# Control.net
KiCad netlist of a schematic drawn in Altium Designer
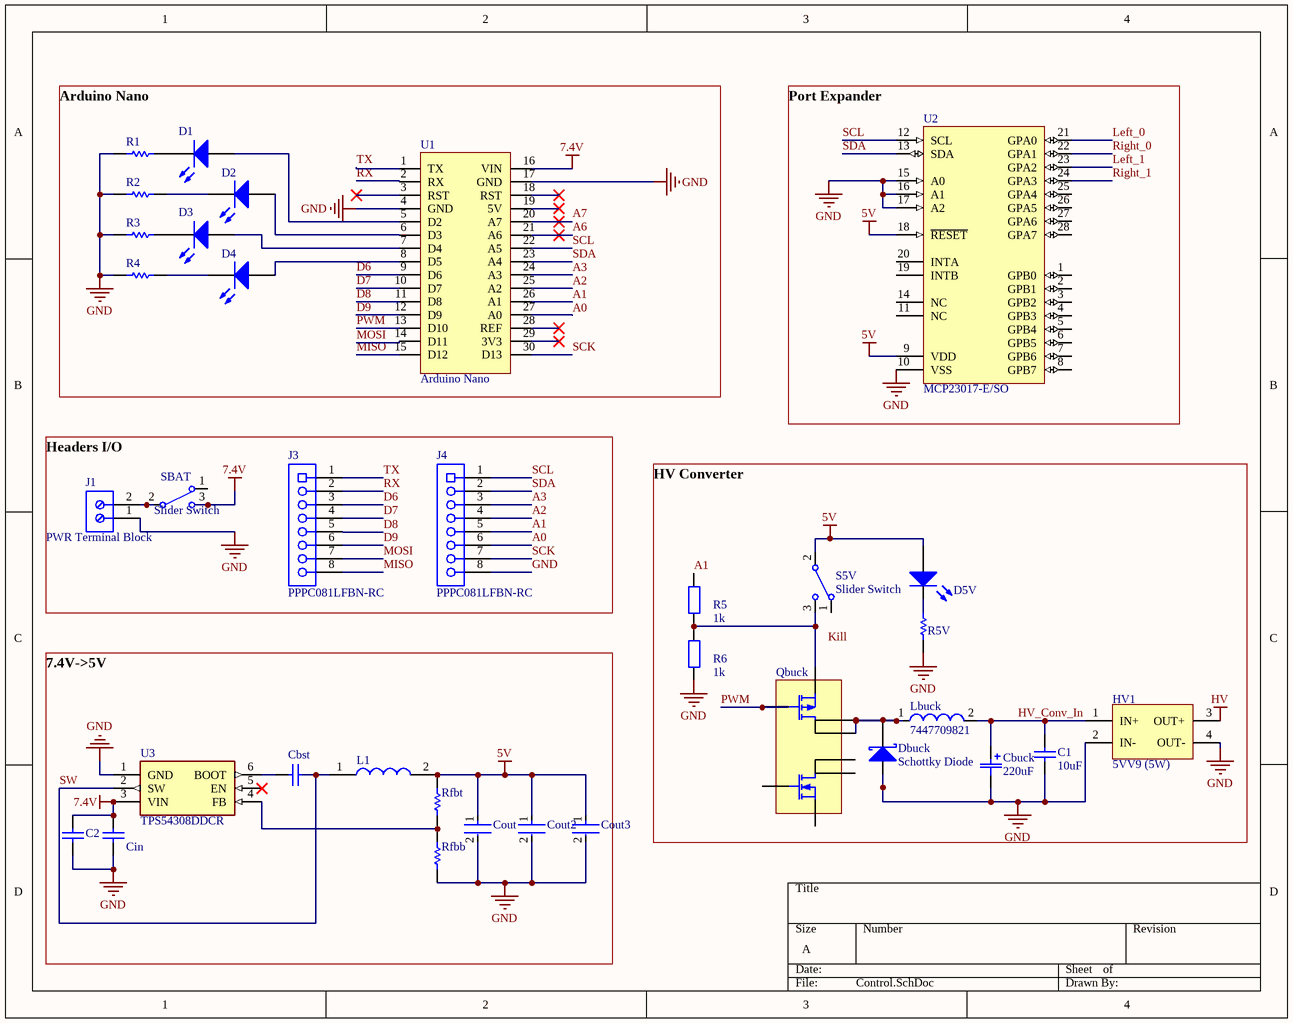
[diagram p0: Control.SchDoc]

(export (version "E")
  (design (tool "Eeschema 10.0.6"))
  (components
    (comp (ref "C1")
      (value "10uF")
      (footprint "1206 CAP")
      (description "1276-3038-6-ND\r\nManufacturer: CL31A106KAHNFNE")
      (fields (field (name "Comment") "Capacitor 10uF"))
      (libsource (lib "Schlib") (part "Capacitor 10uF"))
    )
    (comp (ref "C2")
      (value "C0805C104K5RACTU")
      (footprint "CAPC2013X88X50NL20T25")
      (fields (field (name "MANUFACTURER") "Kemet"))
      (libsource (lib "Altium Content Vault") (part "CAP"))
    )
    (comp (ref "Cbst")
      (value "CAP 100nF 50V 0805(2012)")
      (footprint "CAPC0805(2012)100_M")
      (description "CAP 100nF 50V ±20% 0805 (2012 Metric) Thickness 1mm SMD")
      (fields (field (name "TOLERANCE") "Â±20%"))
      (libsource (lib "Altium Content Vault") (part "CAP"))
    )
    (comp (ref "Cbuck")
      (value "220uF")
      (footprint "SMD 7343 - Pol")
      (description "Digikey: ‎399-8415-1-ND‎\r\nManufacturer: ‎T491X227K016AT‎")
      (fields
        (field (name "Comment") "Capacitor 220uF (Polarized)")
        (field (name "PUBLISHER") "Altium Limited")
      )
      (libsource (lib "Schlib") (part "Capacitor 220uF (Polarized)"))
    )
    (comp (ref "Cin")
      (value "GRM32ER61C226KE20L")
      (footprint "MURA-1210_H_2.7_L")
      (fields (field (name "MANUFACTURER") "Murata") (field (name "TOLERANCE") "±10%"))
      (libsource (lib "Altium Content Vault") (part "CAP-NP-2"))
    )
    (comp (ref "Cout")
      (value "CL32B106KBJNNWE")
      (footprint "FP-CL32-IPC_B")
      (description "Cap Ceramic 10uF 50V X7R ±10% SMD 1210 +125°C Embossed T/R")
      (fields (field (name "TOLERANCE") "10%"))
      (libsource (lib "Altium Content Vault") (part "b4654b650e69147ec39a6b967a45e02"))
    )
    (comp (ref "Cout2")
      (value "CL32B106KBJNNWE")
      (footprint "FP-CL32-IPC_B")
      (description "Cap Ceramic 10uF 50V X7R ±10% SMD 1210 +125°C Embossed T/R")
      (fields (field (name "TOLERANCE") "10%"))
      (libsource (lib "Altium Content Vault") (part "b4654b650e69147ec39a6b967a45e02"))
    )
    (comp (ref "Cout3")
      (value "CL32B106KBJNNWE")
      (footprint "FP-CL32-IPC_B")
      (description "Cap Ceramic 10uF 50V X7R ±10% SMD 1210 +125°C Embossed T/R")
      (fields (field (name "TOLERANCE") "10%"))
      (libsource (lib "Altium Content Vault") (part "b4654b650e69147ec39a6b967a45e02"))
    )
    (comp (ref "D1")
      (value "150080SS75000")
      (footprint "0805_A")
      (description "SMD mono-color Chip LED, WL-SMCW, Super Red")
      (fields (field (name "MANUFACTURER") "Wuerth Elektronik"))
      (libsource (lib "Altium Content Vault") (part "WE-LED_K1A2-2"))
    )
    (comp (ref "D2")
      (value "150080VS75000")
      (footprint "0805_A")
      (description "SMD mono-color Chip LED, WL-SMCW, Bright Green")
      (fields (field (name "MANUFACTURER") "Wuerth Elektronik"))
      (libsource (lib "Altium Content Vault") (part "WE-LED_K1A2-2"))
    )
    (comp (ref "D3")
      (value "150080SS75000")
      (footprint "0805_A")
      (description "SMD mono-color Chip LED, WL-SMCW, Super Red")
      (fields (field (name "MANUFACTURER") "Wuerth Elektronik"))
      (libsource (lib "Altium Content Vault") (part "WE-LED_K1A2-2"))
    )
    (comp (ref "D4")
      (value "150080VS75000")
      (footprint "0805_A")
      (description "SMD mono-color Chip LED, WL-SMCW, Bright Green")
      (fields (field (name "MANUFACTURER") "Wuerth Elektronik"))
      (libsource (lib "Altium Content Vault") (part "WE-LED_K1A2-2"))
    )
    (comp (ref "D5V")
      (value "150080VS75000")
      (footprint "0805_A")
      (description "SMD mono-color Chip LED, WL-SMCW, Bright Green")
      (fields (field (name "MANUFACTURER") "Wuerth Elektronik"))
      (libsource (lib "Altium Content Vault") (part "WE-LED_K1A2-2"))
    )
    (comp (ref "Dbuck")
      (value "Schottky Diode")
      (footprint "Schottky Diode")
      (libsource (lib "Schlib") (part "Schottky Diode"))
    )
    (comp (ref "HV1") (value "5VV9 (5W)") (footprint "5VV9") (libsource (lib "Schlib1") (part "5VV9")))
    (comp (ref "J1")
      (value "PWR Terminal Block")
      (footprint "691103110002")
      (description "Series 1031 - 3.50 mm Horizontal Entry Modular with Pressure Clamp WR-TBL, 2 pin")
      (fields
        (field (name "MANUFACTURER") "Wurth Elektronik")
        (field (name "PART NUMBER") "691103110002")
        (field (name "PUBLISHER") "WurthElektronik")
      )
      (libsource (lib "Altium Content Vault") (part "WE-CN-1P-F-TB2"))
    )
    (comp (ref "J3")
      (value "PPPC081LFBN-RC")
      (footprint "SLIN-PPPC081LFBN-RC_V")
      (libsource (lib "Altium Content Vault") (part "CN-1P-F-R8"))
    )
    (comp (ref "J4")
      (value "PPPC081LFBN-RC")
      (footprint "SLIN-PPPC081LFBN-RC_V")
      (libsource (lib "Altium Content Vault") (part "CN-1P-F-R8"))
    )
    (comp (ref "L1")
      (value "7443251600")
      (footprint "SamacSys:WE-HCI_105023")
      (description "Inductor")
      (fields (field (name "MOUSER PART NUMBER") "710-7443251600"))
      (libsource (lib "*") (part "7443251600"))
    )
    (comp (ref "Lbuck")
      (value "7447709821")
      (footprint "WE-PD-XXL")
      (description "SMD-Shielded Power Inductor WE-PD, L = 820 µH")
      (libsource (lib "Altium Content Vault") (part "PAS-IND-INDUCTOR-2"))
    )
    (comp (ref "Qbuck")
      (value "Dual MOSFET")
      (footprint "SO-8")
      (libsource (lib "Schlib") (part "Dual MOSFET"))
    )
    (comp (ref "R1")
      (value "ERJ-6GEYJ161V")
      (footprint "RESC0805(2012)_N")
      (description "160R 0.125W 5% 0805 (2012 Metric)  SMD")
      (fields (field (name "TOLERANCE") "5 %") (field (name "POWER") "0.125 W"))
      (libsource (lib "Altium Content Vault") (part "RES"))
    )
    (comp (ref "R2")
      (value "ERJ-6GEYJ161V")
      (footprint "RESC0805(2012)_N")
      (description "160R 0.125W 5% 0805 (2012 Metric)  SMD")
      (fields (field (name "TOLERANCE") "5 %") (field (name "POWER") "0.125 W"))
      (libsource (lib "Altium Content Vault") (part "RES"))
    )
    (comp (ref "R3")
      (value "ERJ-6GEYJ161V")
      (footprint "RESC0805(2012)_N")
      (description "160R 0.125W 5% 0805 (2012 Metric)  SMD")
      (fields (field (name "TOLERANCE") "5 %") (field (name "POWER") "0.125 W"))
      (libsource (lib "Altium Content Vault") (part "RES"))
    )
    (comp (ref "R4")
      (value "ERJ-6GEYJ161V")
      (footprint "RESC0805(2012)_N")
      (description "160R 0.125W 5% 0805 (2012 Metric)  SMD")
      (fields (field (name "TOLERANCE") "5 %") (field (name "POWER") "0.125 W"))
      (libsource (lib "Altium Content Vault") (part "RES"))
    )
    (comp (ref "R5")
      (value "1k")
      (footprint "1206 R")
      (description "‎541-2245-1-ND‎\r\nManufacturer: ‎RCA12061K00FKEA‎")
      (fields (field (name "Comment") "Resistor"))
      (libsource (lib "Schlib") (part "Resistor 1k"))
    )
    (comp (ref "R5V")
      (value "ERJ-6GEYJ161V")
      (footprint "RESC0805(2012)_N")
      (description "160R 0.125W 5% 0805 (2012 Metric)  SMD")
      (fields (field (name "TOLERANCE") "5 %") (field (name "POWER") "0.125 W"))
      (libsource (lib "Altium Content Vault") (part "RES"))
    )
    (comp (ref "R6")
      (value "1k")
      (footprint "1206 R")
      (description "‎541-2245-1-ND‎\r\nManufacturer: ‎RCA12061K00FKEA‎")
      (fields (field (name "Comment") "Resistor"))
      (libsource (lib "Schlib") (part "Resistor 1k"))
    )
    (comp (ref "Rfbb")
      (value "CRCW080513K7FKEA")
      (footprint "RESC2013X50X30ML20T20")
      (fields (field (name "MANUFACTURER") "Vishay Dale"))
      (libsource (lib "Altium Content Vault") (part "RES"))
    )
    (comp (ref "Rfbt")
      (value "CRCW0805100KFKEA")
      (footprint "RESC2013X50X30NL20T20")
      (fields (field (name "MANUFACTURER") "Vishay Dale"))
      (libsource (lib "Altium Content Vault") (part "RES"))
    )
    (comp (ref "S5V")
      (value "Slider Switch")
      (footprint "Slide Switch")
      (description "Digikey: ‎563-1571-ND‎\r\nManufacturer:‎ MHS122-1‎")
      (fields (field (name "PUBLISHER") "Altium Limited"))
      (libsource (lib "Schlib") (part "Switch-SPST"))
    )
    (comp (ref "SBAT")
      (value "Slider Switch")
      (footprint "Slide Switch")
      (description "Digikey: ‎563-1571-ND‎\r\nManufacturer:‎ MHS122-1‎")
      (fields (field (name "PUBLISHER") "Altium Limited"))
      (libsource (lib "Schlib") (part "Switch-SPST"))
    )
    (comp (ref "U1")
      (value "Arduino Nano")
      (footprint "Arduino Nano")
      (libsource (lib "Schlib") (part "Arduino Nano"))
    )
    (comp (ref "U2")
      (value "MCP23017-E/SO")
      (footprint "SOIC-SO28_N")
      (description "16-Bit I/O Expander with Serial Interface, 28-Pin SOIC, Extended Temperature")
      (libsource (lib "Altium Content Vault") (part "PR-BUSIC-MCP23017-28"))
    )
    (comp (ref "U3")
      (value "TPS54308DDCR")
      (footprint "SamacSys:SOT95P280X100-6N")
      (description "Power Supply")
      (fields (field (name "MOUSER PART NUMBER") "595-TPS54308DDCR"))
      (libsource (lib "*") (part "TPS54308DDCR"))
    )
  )
  (nets
    (net (code "2") (name "/A0") (class "Default")
      (node (ref "J4") (pin "6") (pinfunction "6_6") (pintype "passive"))
      (node (ref "U1") (pin "27") (pinfunction "A0_27") (pintype "passive"))
    )
    (net (code "3") (name "/A1") (class "Default")
      (node (ref "J4") (pin "5") (pinfunction "5_5") (pintype "passive"))
      (node (ref "R5") (pin "2") (pinfunction "2_2") (pintype "passive"))
      (node (ref "U1") (pin "26") (pinfunction "A1_26") (pintype "passive"))
    )
    (net (code "4") (name "/A2") (class "Default")
      (node (ref "J4") (pin "4") (pinfunction "4_4") (pintype "passive"))
      (node (ref "U1") (pin "25") (pinfunction "A2_25") (pintype "passive"))
    )
    (net (code "5") (name "/A3") (class "Default")
      (node (ref "J4") (pin "3") (pinfunction "3_3") (pintype "passive"))
      (node (ref "U1") (pin "24") (pinfunction "A3_24") (pintype "passive"))
    )
    (net (code "6") (name "/A6") (class "Default")
      (node (ref "U1") (pin "21") (pinfunction "A6_21") (pintype "passive"))
    )
    (net (code "8") (name "/A7") (class "Default")
      (node (ref "U1") (pin "20") (pinfunction "A7_20") (pintype "passive"))
    )
    (net (code "9") (name "/D6") (class "Default")
      (node (ref "J3") (pin "3") (pinfunction "3_3") (pintype "passive"))
      (node (ref "U1") (pin "9") (pinfunction "D6_9") (pintype "passive"))
    )
    (net (code "10") (name "/D7") (class "Default")
      (node (ref "J3") (pin "4") (pinfunction "4_4") (pintype "passive"))
      (node (ref "U1") (pin "10") (pinfunction "D7_10") (pintype "passive"))
    )
    (net (code "11") (name "/D8") (class "Default")
      (node (ref "J3") (pin "5") (pinfunction "5_5") (pintype "passive"))
      (node (ref "U1") (pin "11") (pinfunction "D8_11") (pintype "passive"))
    )
    (net (code "12") (name "/D9") (class "Default")
      (node (ref "J3") (pin "6") (pinfunction "6_6") (pintype "passive"))
      (node (ref "U1") (pin "12") (pinfunction "D9_12") (pintype "passive"))
    )
    (net (code "14") (name "/HV_Conv_In") (class "Default")
      (node (ref "C1") (pin "2") (pinfunction "2_2") (pintype "passive"))
      (node (ref "Cbuck") (pin "1") (pinfunction "1_1") (pintype "passive"))
      (node (ref "HV1") (pin "1") (pinfunction "IN+_1") (pintype "passive"))
      (node (ref "Lbuck") (pin "2") (pinfunction "2_2") (pintype "passive"))
    )
    (net (code "15") (name "/Left_0") (class "Default")
      (node (ref "U2") (pin "21") (pinfunction "GPA0_21") (pintype "bidirectional"))
    )
    (net (code "16") (name "/Left_1") (class "Default")
      (node (ref "U2") (pin "23") (pinfunction "GPA2_23") (pintype "bidirectional"))
    )
    (net (code "17") (name "/MISO") (class "Default")
      (node (ref "J3") (pin "8") (pinfunction "8_8") (pintype "passive"))
      (node (ref "U1") (pin "15") (pinfunction "D12_15") (pintype "passive"))
    )
    (net (code "18") (name "/MOSI") (class "Default")
      (node (ref "J3") (pin "7") (pinfunction "7_7") (pintype "passive"))
      (node (ref "U1") (pin "14") (pinfunction "D11_14") (pintype "passive"))
    )
    (net (code "19") (name "/PWM") (class "Default")
      (node (ref "Qbuck") (pin "4") (pinfunction "4_4") (pintype "passive"))
      (node (ref "U1") (pin "13") (pinfunction "D10_13") (pintype "passive"))
    )
    (net (code "20") (name "/RX") (class "Default")
      (node (ref "J3") (pin "2") (pinfunction "2_2") (pintype "passive"))
      (node (ref "U1") (pin "2") (pinfunction "RX_2") (pintype "passive"))
    )
    (net (code "21") (name "/Right_0") (class "Default")
      (node (ref "U2") (pin "22") (pinfunction "GPA1_22") (pintype "bidirectional"))
    )
    (net (code "22") (name "/Right_1") (class "Default")
      (node (ref "U2") (pin "24") (pinfunction "GPA3_24") (pintype "bidirectional"))
    )
    (net (code "23") (name "/SCK") (class "Default")
      (node (ref "J4") (pin "7") (pinfunction "7_7") (pintype "passive"))
      (node (ref "U1") (pin "30") (pinfunction "D13_30") (pintype "passive"))
    )
    (net (code "24") (name "/SCL") (class "Default")
      (node (ref "J4") (pin "1") (pinfunction "1_1") (pintype "passive"))
      (node (ref "U1") (pin "22") (pinfunction "A5_22") (pintype "passive"))
      (node (ref "U2") (pin "12") (pinfunction "SCL_12") (pintype "input"))
    )
    (net (code "25") (name "/SDA") (class "Default")
      (node (ref "J4") (pin "2") (pinfunction "2_2") (pintype "passive"))
      (node (ref "U1") (pin "23") (pinfunction "A4_23") (pintype "passive"))
      (node (ref "U2") (pin "13") (pinfunction "SDA_13") (pintype "bidirectional"))
    )
    (net (code "26") (name "/SW") (class "Default")
      (node (ref "Cbst") (pin "2") (pinfunction "2_2") (pintype "passive"))
      (node (ref "L1") (pin "1") (pinfunction "1_1") (pintype "passive"))
      (node (ref "U3") (pin "2") (pinfunction "SW_2") (pintype "output"))
    )
    (net (code "27") (name "/TX") (class "Default")
      (node (ref "J3") (pin "1") (pinfunction "1_1") (pintype "passive"))
      (node (ref "U1") (pin "1") (pinfunction "TX_1") (pintype "passive"))
    )
    (net (code "28") (name "5V") (class "Default")
      (node (ref "Cout") (pin "1") (pinfunction "1_1") (pintype "passive"))
      (node (ref "Cout2") (pin "1") (pinfunction "1_1") (pintype "passive"))
      (node (ref "Cout3") (pin "1") (pinfunction "1_1") (pintype "passive"))
      (node (ref "D5V") (pin "2") (pinfunction "A_2") (pintype "passive"))
      (node (ref "L1") (pin "2") (pinfunction "2_2") (pintype "passive"))
      (node (ref "Rfbt") (pin "2") (pinfunction "2_2") (pintype "passive"))
      (node (ref "S5V") (pin "2") (pinfunction "NO_2") (pintype "passive"))
      (node (ref "U2") (pin "18") (pinfunction "~{RESET}_18") (pintype "input"))
      (node (ref "U2") (pin "9") (pinfunction "VDD_9") (pintype "power_in"))
    )
    (net (code "29") (name "7.4V") (class "Default")
      (node (ref "C2") (pin "2") (pinfunction "2_2") (pintype "passive"))
      (node (ref "Cin") (pin "2") (pinfunction "2_2") (pintype "passive"))
      (node (ref "SBAT") (pin "3") (pinfunction "3_3") (pintype "passive"))
      (node (ref "U1") (pin "16") (pinfunction "VIN_16") (pintype "passive"))
      (node (ref "U3") (pin "3") (pinfunction "VIN_3") (pintype "power_in"))
    )
    (net (code "30") (name "GND") (class "Default")
      (node (ref "C1") (pin "1") (pinfunction "1_1") (pintype "passive"))
      (node (ref "C2") (pin "1") (pinfunction "1_1") (pintype "passive"))
      (node (ref "Cbuck") (pin "2") (pinfunction "2_2") (pintype "passive"))
      (node (ref "Cin") (pin "1") (pinfunction "1_1") (pintype "passive"))
      (node (ref "Cout") (pin "2") (pinfunction "2_2") (pintype "passive"))
      (node (ref "Cout2") (pin "2") (pinfunction "2_2") (pintype "passive"))
      (node (ref "Cout3") (pin "2") (pinfunction "2_2") (pintype "passive"))
      (node (ref "Dbuck") (pin "1") (pinfunction "A_1") (pintype "passive"))
      (node (ref "HV1") (pin "2") (pinfunction "IN-_2") (pintype "passive"))
      (node (ref "HV1") (pin "4") (pinfunction "OUT-_4") (pintype "passive"))
      (node (ref "J1") (pin "1") (pinfunction "1_1") (pintype "passive"))
      (node (ref "J4") (pin "8") (pinfunction "8_8") (pintype "passive"))
      (node (ref "R1") (pin "1") (pinfunction "1_1") (pintype "passive"))
      (node (ref "R2") (pin "1") (pinfunction "1_1") (pintype "passive"))
      (node (ref "R3") (pin "1") (pinfunction "1_1") (pintype "passive"))
      (node (ref "R4") (pin "1") (pinfunction "1_1") (pintype "passive"))
      (node (ref "R5V") (pin "1") (pinfunction "1_1") (pintype "passive"))
      (node (ref "R6") (pin "1") (pinfunction "1_1") (pintype "passive"))
      (node (ref "Rfbb") (pin "1") (pinfunction "1_1") (pintype "passive"))
      (node (ref "U1") (pin "17") (pinfunction "GND_17") (pintype "passive"))
      (node (ref "U1") (pin "4") (pinfunction "GND_4") (pintype "passive"))
      (node (ref "U2") (pin "10") (pinfunction "VSS_10") (pintype "power_in"))
      (node (ref "U2") (pin "15") (pinfunction "A0_15") (pintype "input"))
      (node (ref "U2") (pin "16") (pinfunction "A1_16") (pintype "input"))
      (node (ref "U2") (pin "17") (pinfunction "A2_17") (pintype "input"))
      (node (ref "U3") (pin "1") (pinfunction "GND_1") (pintype "power_in"))
    )
    (net (code "31") (name "HV") (class "Default")
      (node (ref "HV1") (pin "3") (pinfunction "OUT+_3") (pintype "passive"))
    )
    (net (code "32") (name "Net-(D1-A)") (class "Default")
      (node (ref "D1") (pin "2") (pinfunction "A_2") (pintype "passive"))
      (node (ref "U1") (pin "5") (pinfunction "D2_5") (pintype "passive"))
    )
    (net (code "33") (name "Net-(D1-K)") (class "Default")
      (node (ref "D1") (pin "1") (pinfunction "K_1") (pintype "passive"))
      (node (ref "R1") (pin "2") (pinfunction "2_2") (pintype "passive"))
    )
    (net (code "34") (name "Net-(D2-A)") (class "Default")
      (node (ref "D2") (pin "2") (pinfunction "A_2") (pintype "passive"))
      (node (ref "U1") (pin "6") (pinfunction "D3_6") (pintype "passive"))
    )
    (net (code "35") (name "Net-(D2-K)") (class "Default")
      (node (ref "D2") (pin "1") (pinfunction "K_1") (pintype "passive"))
      (node (ref "R2") (pin "2") (pinfunction "2_2") (pintype "passive"))
    )
    (net (code "36") (name "Net-(D3-A)") (class "Default")
      (node (ref "D3") (pin "2") (pinfunction "A_2") (pintype "passive"))
      (node (ref "U1") (pin "7") (pinfunction "D4_7") (pintype "passive"))
    )
    (net (code "37") (name "Net-(D3-K)") (class "Default")
      (node (ref "D3") (pin "1") (pinfunction "K_1") (pintype "passive"))
      (node (ref "R3") (pin "2") (pinfunction "2_2") (pintype "passive"))
    )
    (net (code "38") (name "Net-(D4-A)") (class "Default")
      (node (ref "D4") (pin "2") (pinfunction "A_2") (pintype "passive"))
      (node (ref "U1") (pin "8") (pinfunction "D5_8") (pintype "passive"))
    )
    (net (code "39") (name "Net-(D4-K)") (class "Default")
      (node (ref "D4") (pin "1") (pinfunction "K_1") (pintype "passive"))
      (node (ref "R4") (pin "2") (pinfunction "2_2") (pintype "passive"))
    )
    (net (code "40") (name "Net-(D5V-K)") (class "Default")
      (node (ref "D5V") (pin "1") (pinfunction "K_1") (pintype "passive"))
      (node (ref "R5V") (pin "2") (pinfunction "2_2") (pintype "passive"))
    )
    (net (code "41") (name "Net-(Dbuck-K)") (class "Default")
      (node (ref "Dbuck") (pin "2") (pinfunction "K_2") (pintype "passive"))
      (node (ref "Lbuck") (pin "1") (pinfunction "1_1") (pintype "passive"))
      (node (ref "Qbuck") (pin "5") (pinfunction "5_5") (pintype "passive"))
      (node (ref "Qbuck") (pin "6") (pinfunction "6_6") (pintype "passive"))
    )
    (net (code "42") (name "Net-(Qbuck-Pad3)") (class "Default")
      (node (ref "Qbuck") (pin "3") (pinfunction "3_3") (pintype "passive"))
      (node (ref "R5") (pin "1") (pinfunction "1_1") (pintype "passive"))
      (node (ref "R6") (pin "2") (pinfunction "2_2") (pintype "passive"))
      (node (ref "S5V") (pin "3") (pinfunction "3_3") (pintype "passive"))
    )
    (net (code "43") (name "Net-(SBAT-NO)") (class "Default")
      (node (ref "J1") (pin "2") (pinfunction "2_2") (pintype "passive"))
      (node (ref "SBAT") (pin "2") (pinfunction "NO_2") (pintype "passive"))
    )
    (net (code "44") (name "Net-(U3-BOOT)") (class "Default")
      (node (ref "Cbst") (pin "1") (pinfunction "1_1") (pintype "passive"))
      (node (ref "U3") (pin "6") (pinfunction "BOOT_6") (pintype "output"))
    )
    (net (code "45") (name "Net-(U3-FB)") (class "Default")
      (node (ref "Rfbb") (pin "2") (pinfunction "2_2") (pintype "passive"))
      (node (ref "Rfbt") (pin "1") (pinfunction "1_1") (pintype "passive"))
      (node (ref "U3") (pin "4") (pinfunction "FB_4") (pintype "input"))
    )
    (net (code "46") (name "unconnected-(Qbuck-Pad1)") (class "Default")
      (node (ref "Qbuck") (pin "1") (pinfunction "1_1") (pintype "passive"))
    )
    (net (code "47") (name "unconnected-(Qbuck-Pad2)") (class "Default")
      (node (ref "Qbuck") (pin "2") (pinfunction "2_2") (pintype "passive"))
    )
    (net (code "48") (name "unconnected-(Qbuck-Pad7)") (class "Default")
      (node (ref "Qbuck") (pin "7") (pinfunction "7_7") (pintype "passive"))
    )
    (net (code "49") (name "unconnected-(Qbuck-Pad8)") (class "Default")
      (node (ref "Qbuck") (pin "8") (pinfunction "8_8") (pintype "passive"))
    )
    (net (code "50") (name "unconnected-(S5V-COMMON-Pad1)") (class "Default")
      (node (ref "S5V") (pin "1") (pinfunction "COMMON_1") (pintype "passive"))
    )
    (net (code "51") (name "unconnected-(SBAT-COMMON-Pad1)") (class "Default")
      (node (ref "SBAT") (pin "1") (pinfunction "COMMON_1") (pintype "passive"))
    )
    (net (code "52") (name "unconnected-(U1-3V3-Pad29)") (class "Default")
      (node (ref "U1") (pin "29") (pinfunction "3V3_29") (pintype "passive+no_connect"))
    )
    (net (code "53") (name "unconnected-(U1-5V-Pad19)") (class "Default")
      (node (ref "U1") (pin "19") (pinfunction "5V_19") (pintype "passive+no_connect"))
    )
    (net (code "54") (name "unconnected-(U1-REF-Pad28)") (class "Default")
      (node (ref "U1") (pin "28") (pinfunction "REF_28") (pintype "passive+no_connect"))
    )
    (net (code "55") (name "unconnected-(U1-RST-Pad3)") (class "Default")
      (node (ref "U1") (pin "3") (pinfunction "RST_3") (pintype "passive+no_connect"))
    )
    (net (code "56") (name "unconnected-(U1-RST-Pad18)") (class "Default")
      (node (ref "U1") (pin "18") (pinfunction "RST_18") (pintype "passive+no_connect"))
    )
    (net (code "57") (name "unconnected-(U2-GPA4-Pad25)") (class "Default")
      (node (ref "U2") (pin "25") (pinfunction "GPA4_25") (pintype "bidirectional"))
    )
    (net (code "58") (name "unconnected-(U2-GPA5-Pad26)") (class "Default")
      (node (ref "U2") (pin "26") (pinfunction "GPA5_26") (pintype "bidirectional"))
    )
    (net (code "59") (name "unconnected-(U2-GPA6-Pad27)") (class "Default")
      (node (ref "U2") (pin "27") (pinfunction "GPA6_27") (pintype "bidirectional"))
    )
    (net (code "60") (name "unconnected-(U2-GPA7-Pad28)") (class "Default")
      (node (ref "U2") (pin "28") (pinfunction "GPA7_28") (pintype "bidirectional"))
    )
    (net (code "61") (name "unconnected-(U2-GPB0-Pad1)") (class "Default")
      (node (ref "U2") (pin "1") (pinfunction "GPB0_1") (pintype "bidirectional"))
    )
    (net (code "62") (name "unconnected-(U2-GPB1-Pad2)") (class "Default")
      (node (ref "U2") (pin "2") (pinfunction "GPB1_2") (pintype "bidirectional"))
    )
    (net (code "63") (name "unconnected-(U2-GPB2-Pad3)") (class "Default")
      (node (ref "U2") (pin "3") (pinfunction "GPB2_3") (pintype "bidirectional"))
    )
    (net (code "64") (name "unconnected-(U2-GPB3-Pad4)") (class "Default")
      (node (ref "U2") (pin "4") (pinfunction "GPB3_4") (pintype "bidirectional"))
    )
    (net (code "65") (name "unconnected-(U2-GPB4-Pad5)") (class "Default")
      (node (ref "U2") (pin "5") (pinfunction "GPB4_5") (pintype "bidirectional"))
    )
    (net (code "66") (name "unconnected-(U2-GPB5-Pad6)") (class "Default")
      (node (ref "U2") (pin "6") (pinfunction "GPB5_6") (pintype "bidirectional"))
    )
    (net (code "67") (name "unconnected-(U2-GPB6-Pad7)") (class "Default")
      (node (ref "U2") (pin "7") (pinfunction "GPB6_7") (pintype "bidirectional"))
    )
    (net (code "68") (name "unconnected-(U2-GPB7-Pad8)") (class "Default")
      (node (ref "U2") (pin "8") (pinfunction "GPB7_8") (pintype "bidirectional"))
    )
    (net (code "69") (name "unconnected-(U2-INTA-Pad20)") (class "Default")
      (node (ref "U2") (pin "20") (pinfunction "INTA_20") (pintype "open_collector"))
    )
    (net (code "70") (name "unconnected-(U2-INTB-Pad19)") (class "Default")
      (node (ref "U2") (pin "19") (pinfunction "INTB_19") (pintype "open_collector"))
    )
    (net (code "71") (name "unconnected-(U2-NC-Pad11)") (class "Default")
      (node (ref "U2") (pin "11") (pinfunction "NC_11") (pintype "passive"))
    )
    (net (code "72") (name "unconnected-(U2-NC-Pad14)") (class "Default")
      (node (ref "U2") (pin "14") (pinfunction "NC_14") (pintype "passive"))
    )
    (net (code "73") (name "unconnected-(U3-EN-Pad5)") (class "Default")
      (node (ref "U3") (pin "5") (pinfunction "EN_5") (pintype "input+no_connect"))
    )
  )
)
